# cpu_board.net
KiCad netlist of a schematic drawn in EAGLE
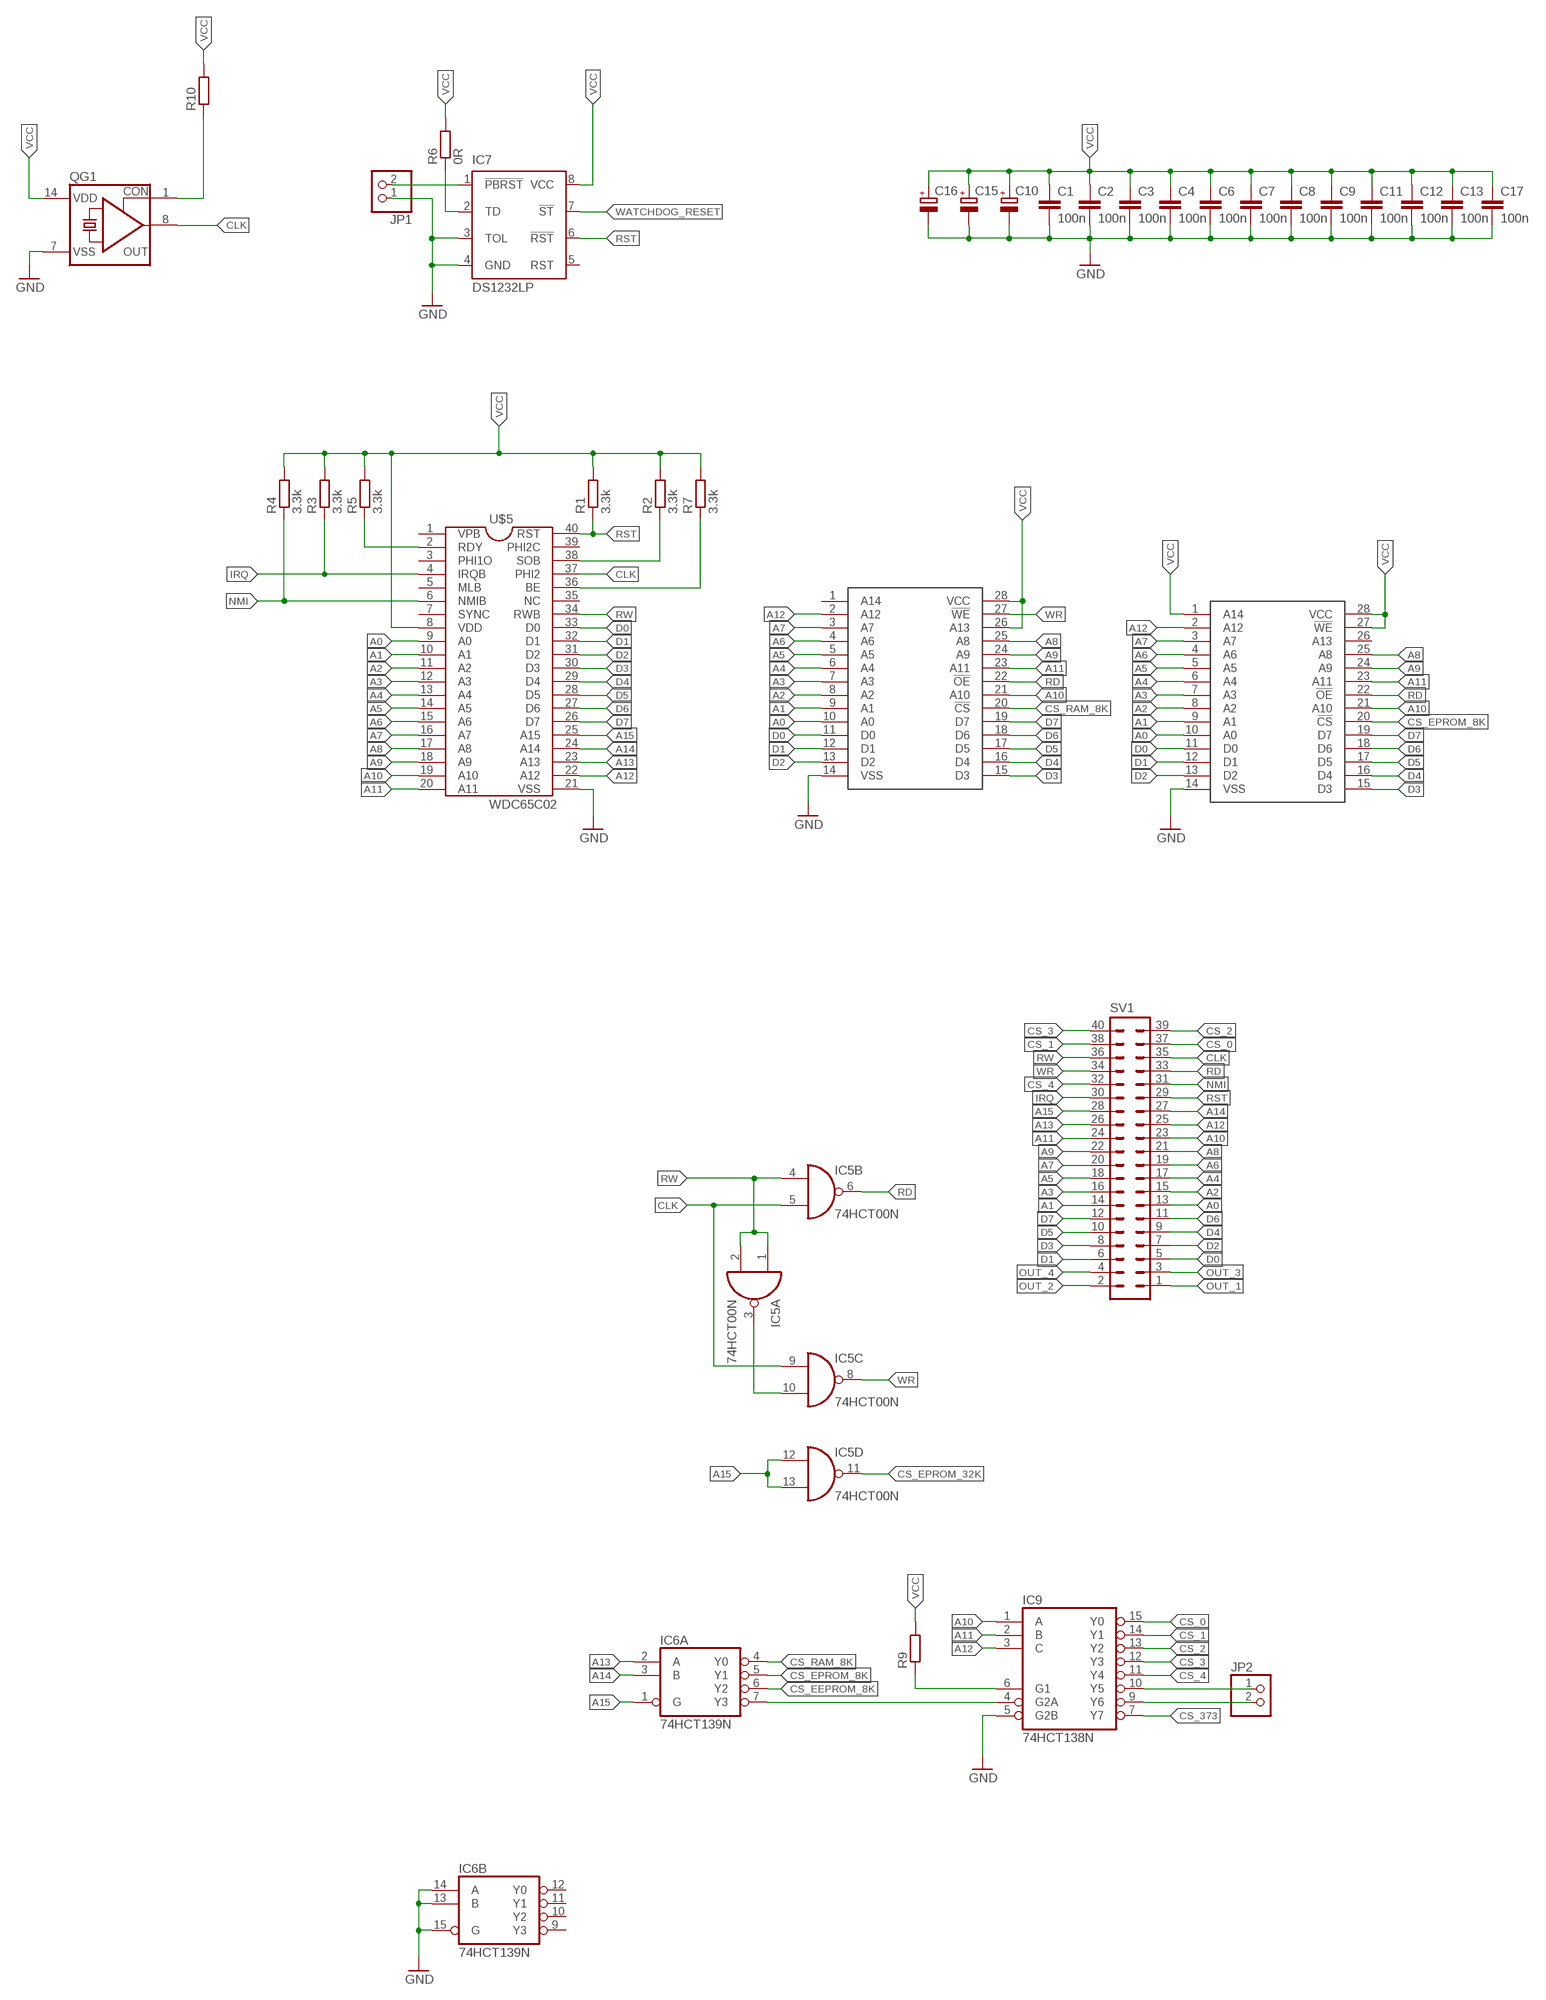
[diagram p0: schematic, sheet 1, part 1 of 2]
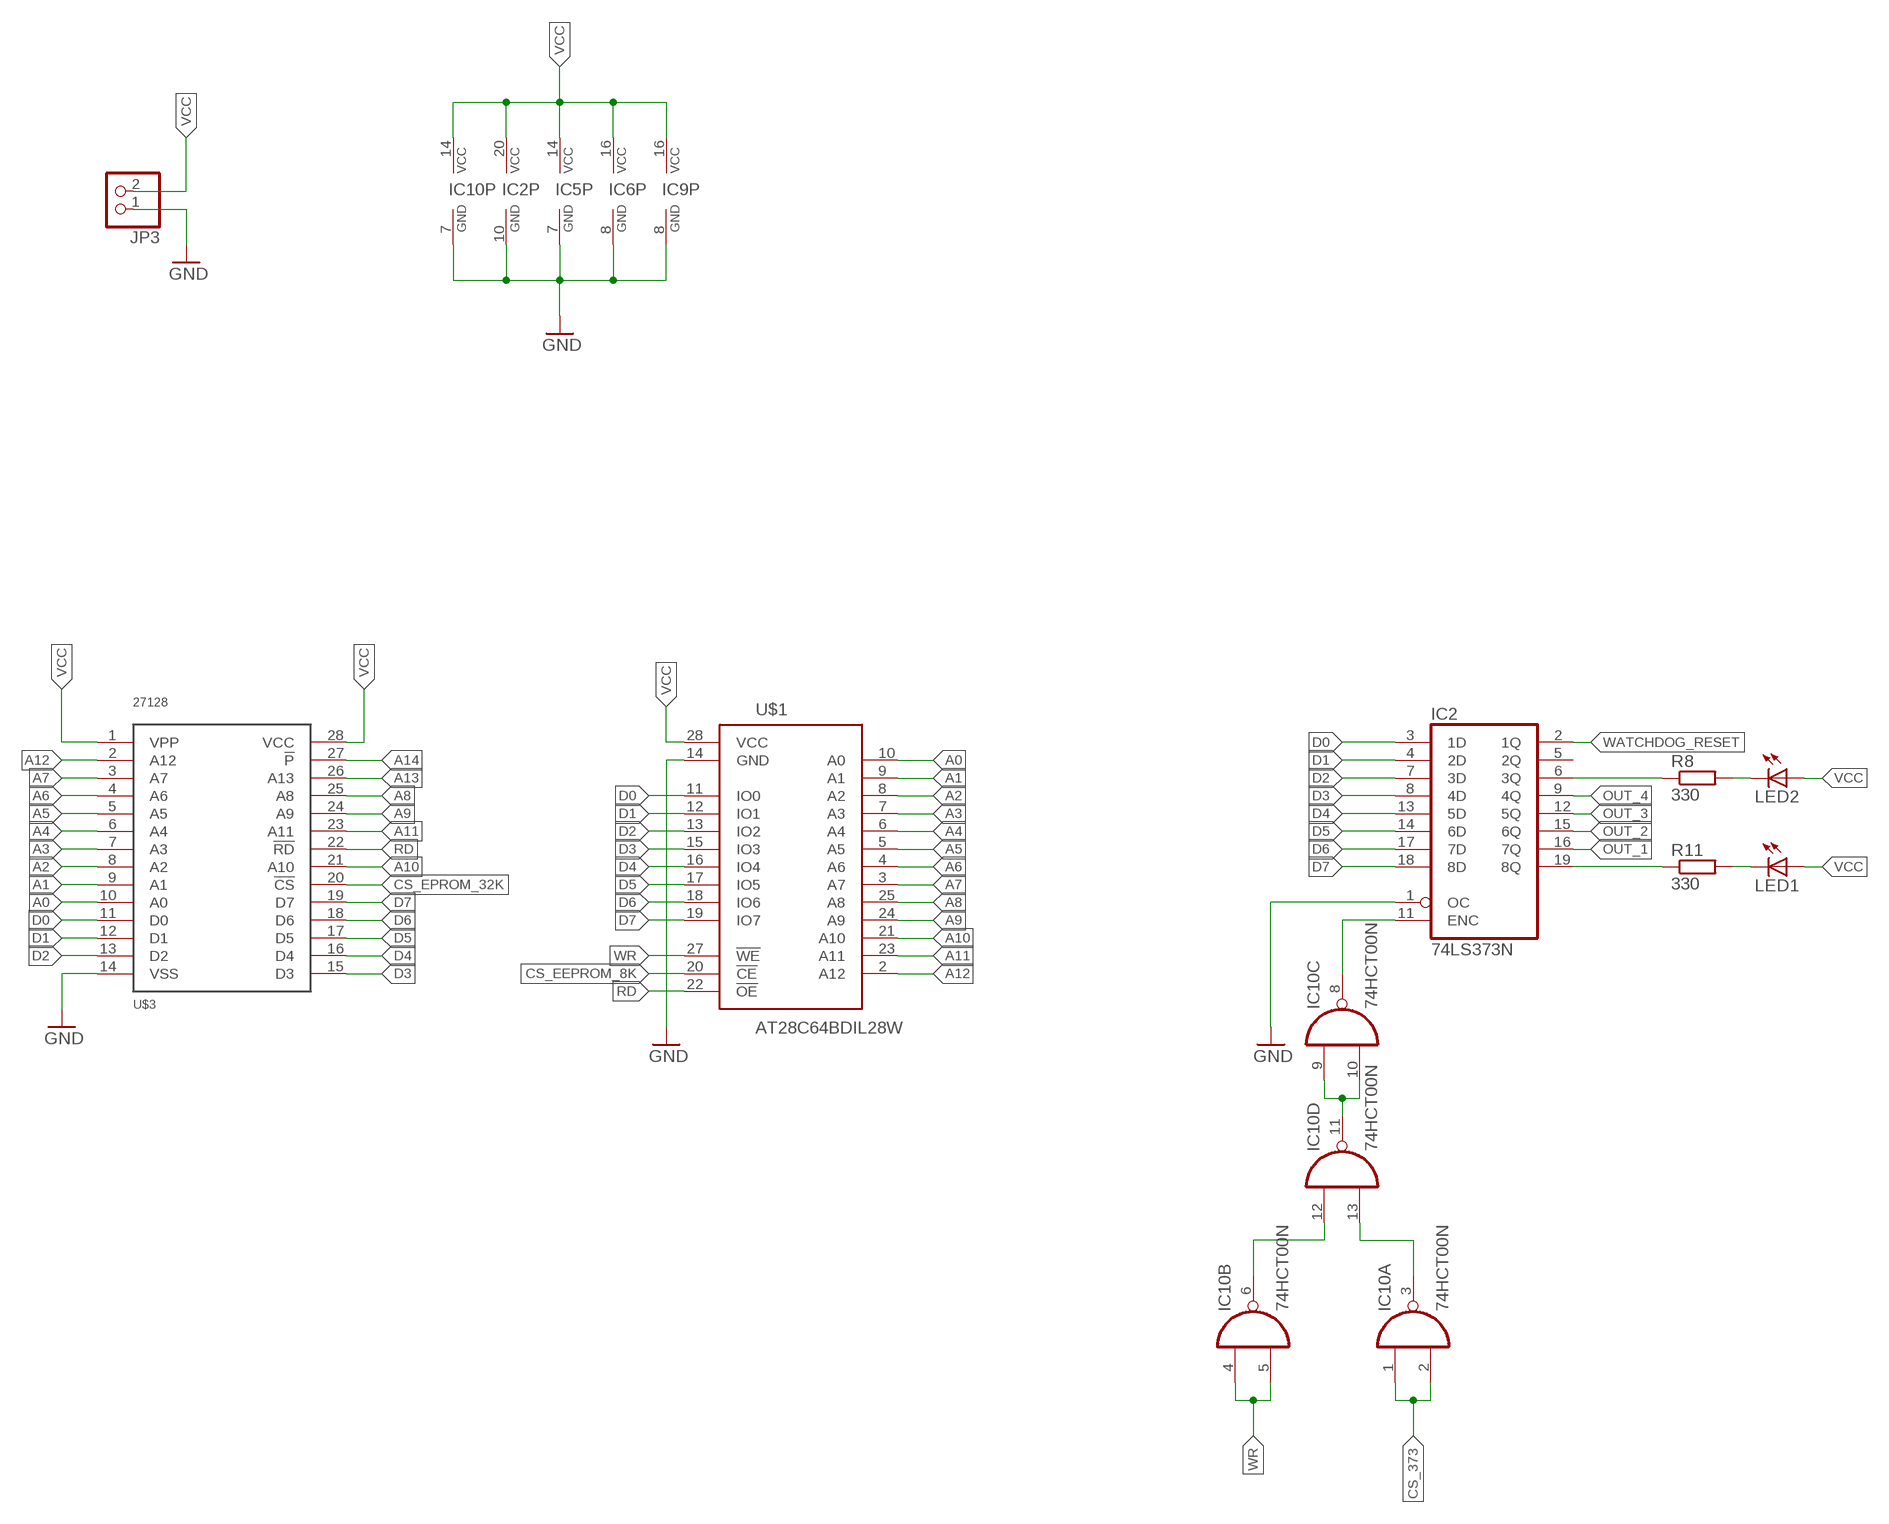
[diagram p1: schematic, sheet 1, part 2 of 2]

(export (version "E")
  (design (tool "Eeschema 10.0.6"))
  (components
    (comp (ref "C1")
      (value "100n")
      (footprint "eagle-import:C1206")
      (libsource (lib "eagle-import") (part "C-EUC1206"))
    )
    (comp (ref "C2")
      (value "100n")
      (footprint "eagle-import:C1206")
      (libsource (lib "eagle-import") (part "C-EUC1206"))
    )
    (comp (ref "C3")
      (value "100n")
      (footprint "eagle-import:C1206")
      (libsource (lib "eagle-import") (part "C-EUC1206"))
    )
    (comp (ref "C4")
      (value "100n")
      (footprint "eagle-import:C1206")
      (libsource (lib "eagle-import") (part "C-EUC1206"))
    )
    (comp (ref "C6")
      (value "100n")
      (footprint "eagle-import:C1206")
      (libsource (lib "eagle-import") (part "C-EUC1206"))
    )
    (comp (ref "C7")
      (value "100n")
      (footprint "eagle-import:C1206")
      (libsource (lib "eagle-import") (part "C-EUC1206"))
    )
    (comp (ref "C8")
      (value "100n")
      (footprint "eagle-import:C1206")
      (libsource (lib "eagle-import") (part "C-EUC1206"))
    )
    (comp (ref "C9")
      (value "100n")
      (footprint "eagle-import:C1206")
      (libsource (lib "eagle-import") (part "C-EUC1206"))
    )
    (comp (ref "C10")
      (value "CPOL-EUE5-10.5")
      (footprint "eagle-import:E5-10,5")
      (libsource (lib "eagle-import") (part "CPOL-EUE5-10.5"))
    )
    (comp (ref "C11")
      (value "100n")
      (footprint "eagle-import:C0805")
      (libsource (lib "eagle-import") (part "C-EUC0805"))
    )
    (comp (ref "C12")
      (value "100n")
      (footprint "eagle-import:C0805")
      (libsource (lib "eagle-import") (part "C-EUC0805"))
    )
    (comp (ref "C13")
      (value "100n")
      (footprint "eagle-import:C0805")
      (libsource (lib "eagle-import") (part "C-EUC0805"))
    )
    (comp (ref "C15")
      (value "CPOL-EUSMCB")
      (footprint "eagle-import:SMC_B")
      (libsource (lib "eagle-import") (part "CPOL-EUSMCB"))
    )
    (comp (ref "C16")
      (value "CPOL-EUSMCB")
      (footprint "eagle-import:SMC_B")
      (libsource (lib "eagle-import") (part "CPOL-EUSMCB"))
    )
    (comp (ref "C17")
      (value "100n")
      (footprint "eagle-import:C1206")
      (libsource (lib "eagle-import") (part "C-EUC1206"))
    )
    (comp (ref "IC2")
      (value "74LS373N")
      (footprint "eagle-import:DIL20")
      (libsource (lib "eagle-import") (part "74373NLS"))
    )
    (comp (ref "IC5")
      (value "74HCT00N")
      (footprint "eagle-import:DIL14")
      (libsource (lib "eagle-import") (part "7400NHCT"))
    )
    (comp (ref "IC6")
      (value "74HCT139N")
      (footprint "eagle-import:DIL16")
      (libsource (lib "eagle-import") (part "74139NHCT"))
    )
    (comp (ref "IC7")
      (value "DS1232LP")
      (footprint "eagle-import:DIL08")
      (fields (field (name "MPN") "DS1232LP+"))
      (libsource (lib "eagle-import") (part "DS1232LP"))
    )
    (comp (ref "IC9")
      (value "74HCT138N")
      (footprint "eagle-import:DIL16")
      (libsource (lib "eagle-import") (part "74138NHCT"))
    )
    (comp (ref "IC10")
      (value "74HCT00N")
      (footprint "eagle-import:DIL14")
      (libsource (lib "eagle-import") (part "7400NHCT"))
    )
    (comp (ref "JP1")
      (value "PINHD-1X2")
      (footprint "eagle-import:1X02")
      (libsource (lib "eagle-import") (part "PINHD-1X2"))
    )
    (comp (ref "JP2")
      (value "PINHD-1X2")
      (footprint "eagle-import:1X02")
      (libsource (lib "eagle-import") (part "PINHD-1X2"))
    )
    (comp (ref "JP3")
      (value "PINHD-1X2/90")
      (footprint "eagle-import:1X02_90")
      (libsource (lib "eagle-import") (part "PINHD-1X2/90"))
    )
    (comp (ref "LED1")
      (value "LED5MM")
      (footprint "eagle-import:LED5MM")
      (libsource (lib "eagle-import") (part "LED5MM"))
    )
    (comp (ref "LED2")
      (value "LED5MM")
      (footprint "eagle-import:LED5MM")
      (libsource (lib "eagle-import") (part "LED5MM"))
    )
    (comp (ref "QG1")
      (value "CRYSTAL_RES-SG51")
      (footprint "eagle-import:SG51")
      (libsource (lib "eagle-import") (part "CRYSTAL_RES-SG51"))
    )
    (comp (ref "R1")
      (value "3.3k")
      (footprint "eagle-import:R1206")
      (libsource (lib "eagle-import") (part "R-EU_R1206"))
    )
    (comp (ref "R2")
      (value "3.3k")
      (footprint "eagle-import:R1206")
      (libsource (lib "eagle-import") (part "R-EU_R1206"))
    )
    (comp (ref "R3")
      (value "3.3k")
      (footprint "eagle-import:R1206")
      (libsource (lib "eagle-import") (part "R-EU_R1206"))
    )
    (comp (ref "R4")
      (value "3.3k")
      (footprint "eagle-import:R1206")
      (libsource (lib "eagle-import") (part "R-EU_R1206"))
    )
    (comp (ref "R5")
      (value "3.3k")
      (footprint "eagle-import:R1206")
      (libsource (lib "eagle-import") (part "R-EU_R1206"))
    )
    (comp (ref "R6")
      (value "0R")
      (footprint "eagle-import:R1206")
      (libsource (lib "eagle-import") (part "R-EU_R1206"))
    )
    (comp (ref "R7")
      (value "3.3k")
      (footprint "eagle-import:R1206")
      (libsource (lib "eagle-import") (part "R-EU_R1206"))
    )
    (comp (ref "R8")
      (value "330")
      (footprint "eagle-import:R1206")
      (libsource (lib "eagle-import") (part "R-EU_R1206"))
    )
    (comp (ref "R9")
      (value "R-EU_0204/7")
      (footprint "eagle-import:0204_7")
      (libsource (lib "eagle-import") (part "R-EU_0204/7"))
    )
    (comp (ref "R10")
      (value "R-EU_R1206")
      (footprint "eagle-import:R1206")
      (libsource (lib "eagle-import") (part "R-EU_R1206"))
    )
    (comp (ref "R11")
      (value "330")
      (footprint "eagle-import:R1206")
      (libsource (lib "eagle-import") (part "R-EU_R1206"))
    )
    (comp (ref "SV1")
      (value "ML40L")
      (footprint "eagle-import:ML40L")
      (libsource (lib "eagle-import") (part "ML40L"))
    )
    (comp (ref "U$1")
      (value "AT28C64BDIL28W")
      (footprint "eagle-import:DIL28-6")
      (libsource (lib "eagle-import") (part "AT28C64BDIL28W"))
    )
    (comp (ref "U$2")
      (value "62256")
      (footprint "eagle-import:DIL28-6")
      (libsource (lib "eagle-import") (part "62256"))
    )
    (comp (ref "U$3")
      (value "27128")
      (footprint "eagle-import:DIL28")
      (libsource (lib "eagle-import") (part "27128"))
    )
    (comp (ref "U$4")
      (value "62256")
      (footprint "eagle-import:DIL28-6")
      (libsource (lib "eagle-import") (part "62256"))
    )
    (comp (ref "U$5")
      (value "WDC65C02")
      (footprint "eagle-import:DIL40")
      (libsource (lib "eagle-import") (part "WDC65C02"))
    )
  )
  (nets
    (net (code "1") (name "A0") (class "Default")
      (node (ref "SV1") (pin "13") (pinfunction "13_13") (pintype "passive"))
      (node (ref "U$1") (pin "10") (pinfunction "A0_10") (pintype "bidirectional"))
      (node (ref "U$2") (pin "10") (pinfunction "A0_10") (pintype "bidirectional"))
      (node (ref "U$3") (pin "10") (pinfunction "A0_10") (pintype "bidirectional"))
      (node (ref "U$4") (pin "10") (pinfunction "A0_10") (pintype "bidirectional"))
      (node (ref "U$5") (pin "9") (pinfunction "A0_9") (pintype "bidirectional"))
    )
    (net (code "2") (name "A1") (class "Default")
      (node (ref "SV1") (pin "14") (pinfunction "14_14") (pintype "passive"))
      (node (ref "U$1") (pin "9") (pinfunction "A1_9") (pintype "bidirectional"))
      (node (ref "U$2") (pin "9") (pinfunction "A1_9") (pintype "bidirectional"))
      (node (ref "U$3") (pin "9") (pinfunction "A1_9") (pintype "bidirectional"))
      (node (ref "U$4") (pin "9") (pinfunction "A1_9") (pintype "bidirectional"))
      (node (ref "U$5") (pin "10") (pinfunction "A1_10") (pintype "bidirectional"))
    )
    (net (code "3") (name "A2") (class "Default")
      (node (ref "SV1") (pin "15") (pinfunction "15_15") (pintype "passive"))
      (node (ref "U$1") (pin "8") (pinfunction "A2_8") (pintype "bidirectional"))
      (node (ref "U$2") (pin "8") (pinfunction "A2_8") (pintype "bidirectional"))
      (node (ref "U$3") (pin "8") (pinfunction "A2_8") (pintype "bidirectional"))
      (node (ref "U$4") (pin "8") (pinfunction "A2_8") (pintype "bidirectional"))
      (node (ref "U$5") (pin "11") (pinfunction "A2_11") (pintype "bidirectional"))
    )
    (net (code "4") (name "A3") (class "Default")
      (node (ref "SV1") (pin "16") (pinfunction "16_16") (pintype "passive"))
      (node (ref "U$1") (pin "7") (pinfunction "A3_7") (pintype "bidirectional"))
      (node (ref "U$2") (pin "7") (pinfunction "A3_7") (pintype "bidirectional"))
      (node (ref "U$3") (pin "7") (pinfunction "A3_7") (pintype "bidirectional"))
      (node (ref "U$4") (pin "7") (pinfunction "A3_7") (pintype "bidirectional"))
      (node (ref "U$5") (pin "12") (pinfunction "A3_12") (pintype "bidirectional"))
    )
    (net (code "5") (name "A4") (class "Default")
      (node (ref "SV1") (pin "17") (pinfunction "17_17") (pintype "passive"))
      (node (ref "U$1") (pin "6") (pinfunction "A4_6") (pintype "bidirectional"))
      (node (ref "U$2") (pin "6") (pinfunction "A4_6") (pintype "bidirectional"))
      (node (ref "U$3") (pin "6") (pinfunction "A4_6") (pintype "bidirectional"))
      (node (ref "U$4") (pin "6") (pinfunction "A4_6") (pintype "bidirectional"))
      (node (ref "U$5") (pin "13") (pinfunction "A4_13") (pintype "bidirectional"))
    )
    (net (code "6") (name "A5") (class "Default")
      (node (ref "SV1") (pin "18") (pinfunction "18_18") (pintype "passive"))
      (node (ref "U$1") (pin "5") (pinfunction "A5_5") (pintype "bidirectional"))
      (node (ref "U$2") (pin "5") (pinfunction "A5_5") (pintype "bidirectional"))
      (node (ref "U$3") (pin "5") (pinfunction "A5_5") (pintype "bidirectional"))
      (node (ref "U$4") (pin "5") (pinfunction "A5_5") (pintype "bidirectional"))
      (node (ref "U$5") (pin "14") (pinfunction "A5_14") (pintype "bidirectional"))
    )
    (net (code "7") (name "A6") (class "Default")
      (node (ref "SV1") (pin "19") (pinfunction "19_19") (pintype "passive"))
      (node (ref "U$1") (pin "4") (pinfunction "A6_4") (pintype "bidirectional"))
      (node (ref "U$2") (pin "4") (pinfunction "A6_4") (pintype "bidirectional"))
      (node (ref "U$3") (pin "4") (pinfunction "A6_4") (pintype "bidirectional"))
      (node (ref "U$4") (pin "4") (pinfunction "A6_4") (pintype "bidirectional"))
      (node (ref "U$5") (pin "15") (pinfunction "A6_15") (pintype "bidirectional"))
    )
    (net (code "8") (name "A7") (class "Default")
      (node (ref "SV1") (pin "20") (pinfunction "20_20") (pintype "passive"))
      (node (ref "U$1") (pin "3") (pinfunction "A7_3") (pintype "bidirectional"))
      (node (ref "U$2") (pin "3") (pinfunction "A7_3") (pintype "bidirectional"))
      (node (ref "U$3") (pin "3") (pinfunction "A7_3") (pintype "bidirectional"))
      (node (ref "U$4") (pin "3") (pinfunction "A7_3") (pintype "bidirectional"))
      (node (ref "U$5") (pin "16") (pinfunction "A7_16") (pintype "bidirectional"))
    )
    (net (code "9") (name "A8") (class "Default")
      (node (ref "SV1") (pin "21") (pinfunction "21_21") (pintype "passive"))
      (node (ref "U$1") (pin "25") (pinfunction "A8_25") (pintype "bidirectional"))
      (node (ref "U$2") (pin "25") (pinfunction "A8_25") (pintype "bidirectional"))
      (node (ref "U$3") (pin "25") (pinfunction "A8_25") (pintype "bidirectional"))
      (node (ref "U$4") (pin "25") (pinfunction "A8_25") (pintype "bidirectional"))
      (node (ref "U$5") (pin "17") (pinfunction "A8_17") (pintype "bidirectional"))
    )
    (net (code "10") (name "A9") (class "Default")
      (node (ref "SV1") (pin "22") (pinfunction "22_22") (pintype "passive"))
      (node (ref "U$1") (pin "24") (pinfunction "A9_24") (pintype "bidirectional"))
      (node (ref "U$2") (pin "24") (pinfunction "A9_24") (pintype "bidirectional"))
      (node (ref "U$3") (pin "24") (pinfunction "A9_24") (pintype "bidirectional"))
      (node (ref "U$4") (pin "24") (pinfunction "A9_24") (pintype "bidirectional"))
      (node (ref "U$5") (pin "18") (pinfunction "A9_18") (pintype "bidirectional"))
    )
    (net (code "11") (name "A10") (class "Default")
      (node (ref "IC9") (pin "1") (pinfunction "A_1") (pintype "input"))
      (node (ref "SV1") (pin "23") (pinfunction "23_23") (pintype "passive"))
      (node (ref "U$1") (pin "21") (pinfunction "A10_21") (pintype "bidirectional"))
      (node (ref "U$2") (pin "21") (pinfunction "A10_21") (pintype "bidirectional"))
      (node (ref "U$3") (pin "21") (pinfunction "A10_21") (pintype "bidirectional"))
      (node (ref "U$4") (pin "21") (pinfunction "A10_21") (pintype "bidirectional"))
      (node (ref "U$5") (pin "19") (pinfunction "A10_19") (pintype "bidirectional"))
    )
    (net (code "12") (name "A11") (class "Default")
      (node (ref "IC9") (pin "2") (pinfunction "B_2") (pintype "input"))
      (node (ref "SV1") (pin "24") (pinfunction "24_24") (pintype "passive"))
      (node (ref "U$1") (pin "23") (pinfunction "A11_23") (pintype "bidirectional"))
      (node (ref "U$2") (pin "23") (pinfunction "A11_23") (pintype "bidirectional"))
      (node (ref "U$3") (pin "23") (pinfunction "A11_23") (pintype "bidirectional"))
      (node (ref "U$4") (pin "23") (pinfunction "A11_23") (pintype "bidirectional"))
      (node (ref "U$5") (pin "20") (pinfunction "A11_20") (pintype "bidirectional"))
    )
    (net (code "13") (name "A12") (class "Default")
      (node (ref "IC9") (pin "3") (pinfunction "C_3") (pintype "input"))
      (node (ref "SV1") (pin "25") (pinfunction "25_25") (pintype "passive"))
      (node (ref "U$1") (pin "2") (pinfunction "A12_2") (pintype "bidirectional"))
      (node (ref "U$2") (pin "2") (pinfunction "A12_2") (pintype "bidirectional"))
      (node (ref "U$3") (pin "2") (pinfunction "A12_2") (pintype "bidirectional"))
      (node (ref "U$4") (pin "2") (pinfunction "A12_2") (pintype "bidirectional"))
      (node (ref "U$5") (pin "22") (pinfunction "A12_22") (pintype "bidirectional"))
    )
    (net (code "14") (name "A13") (class "Default")
      (node (ref "IC6") (pin "2") (pinfunction "A_2") (pintype "input"))
      (node (ref "SV1") (pin "26") (pinfunction "26_26") (pintype "passive"))
      (node (ref "U$3") (pin "26") (pinfunction "A13_26") (pintype "bidirectional"))
      (node (ref "U$5") (pin "23") (pinfunction "A13_23") (pintype "bidirectional"))
    )
    (net (code "15") (name "A14") (class "Default")
      (node (ref "IC6") (pin "3") (pinfunction "B_3") (pintype "input"))
      (node (ref "SV1") (pin "27") (pinfunction "27_27") (pintype "passive"))
      (node (ref "U$3") (pin "27") (pinfunction "~{P}_27") (pintype "bidirectional"))
      (node (ref "U$5") (pin "24") (pinfunction "A14_24") (pintype "bidirectional"))
    )
    (net (code "16") (name "A15") (class "Default")
      (node (ref "IC5") (pin "12") (pinfunction "I0_12") (pintype "input"))
      (node (ref "IC5") (pin "13") (pinfunction "I1_13") (pintype "input"))
      (node (ref "IC6") (pin "1") (pinfunction "G_1") (pintype "input"))
      (node (ref "SV1") (pin "28") (pinfunction "28_28") (pintype "passive"))
      (node (ref "U$5") (pin "25") (pinfunction "A15_25") (pintype "bidirectional"))
    )
    (net (code "17") (name "CLK") (class "Default")
      (node (ref "IC5") (pin "5") (pinfunction "I1_5") (pintype "input"))
      (node (ref "IC5") (pin "9") (pinfunction "I0_9") (pintype "input"))
      (node (ref "QG1") (pin "8") (pinfunction "OUT_8") (pintype "output"))
      (node (ref "SV1") (pin "35") (pinfunction "35_35") (pintype "passive"))
      (node (ref "U$5") (pin "37") (pinfunction "PHI2_37") (pintype "bidirectional"))
    )
    (net (code "18") (name "CS_0") (class "Default")
      (node (ref "IC9") (pin "15") (pinfunction "Y0_15") (pintype "output"))
      (node (ref "SV1") (pin "37") (pinfunction "37_37") (pintype "passive"))
    )
    (net (code "19") (name "CS_1") (class "Default")
      (node (ref "IC9") (pin "14") (pinfunction "Y1_14") (pintype "output"))
      (node (ref "SV1") (pin "38") (pinfunction "38_38") (pintype "passive"))
    )
    (net (code "20") (name "CS_2") (class "Default")
      (node (ref "IC9") (pin "13") (pinfunction "Y2_13") (pintype "output"))
      (node (ref "SV1") (pin "39") (pinfunction "39_39") (pintype "passive"))
    )
    (net (code "21") (name "CS_3") (class "Default")
      (node (ref "IC9") (pin "12") (pinfunction "Y3_12") (pintype "output"))
      (node (ref "SV1") (pin "40") (pinfunction "40_40") (pintype "passive"))
    )
    (net (code "22") (name "CS_4") (class "Default")
      (node (ref "IC9") (pin "11") (pinfunction "Y4_11") (pintype "output"))
      (node (ref "SV1") (pin "32") (pinfunction "32_32") (pintype "passive"))
    )
    (net (code "23") (name "CS_373") (class "Default")
      (node (ref "IC10") (pin "1") (pinfunction "I0_1") (pintype "input"))
      (node (ref "IC10") (pin "2") (pinfunction "I1_2") (pintype "input"))
      (node (ref "IC9") (pin "7") (pinfunction "Y7_7") (pintype "output"))
    )
    (net (code "24") (name "CS_EEPROM_8K") (class "Default")
      (node (ref "IC6") (pin "6") (pinfunction "Y2_6") (pintype "output"))
      (node (ref "U$1") (pin "20") (pinfunction "~{CE}_20") (pintype "bidirectional"))
    )
    (net (code "25") (name "CS_EPROM_8K") (class "Default")
      (node (ref "IC6") (pin "5") (pinfunction "Y1_5") (pintype "output"))
      (node (ref "U$2") (pin "20") (pinfunction "~{CS}_20") (pintype "bidirectional"))
    )
    (net (code "26") (name "CS_EPROM_32K") (class "Default")
      (node (ref "IC5") (pin "11") (pinfunction "O_11") (pintype "output"))
      (node (ref "U$3") (pin "20") (pinfunction "~{CS}_20") (pintype "bidirectional"))
    )
    (net (code "27") (name "CS_RAM_8K") (class "Default")
      (node (ref "IC6") (pin "4") (pinfunction "Y0_4") (pintype "output"))
      (node (ref "U$4") (pin "20") (pinfunction "~{CS}_20") (pintype "bidirectional"))
    )
    (net (code "28") (name "D0") (class "Default")
      (node (ref "IC2") (pin "3") (pinfunction "1D_3") (pintype "input"))
      (node (ref "SV1") (pin "5") (pinfunction "5_5") (pintype "passive"))
      (node (ref "U$1") (pin "11") (pinfunction "IO0_11") (pintype "bidirectional"))
      (node (ref "U$2") (pin "11") (pinfunction "D0_11") (pintype "bidirectional"))
      (node (ref "U$3") (pin "11") (pinfunction "D0_11") (pintype "bidirectional"))
      (node (ref "U$4") (pin "11") (pinfunction "D0_11") (pintype "bidirectional"))
      (node (ref "U$5") (pin "33") (pinfunction "D0_33") (pintype "bidirectional"))
    )
    (net (code "29") (name "D1") (class "Default")
      (node (ref "IC2") (pin "4") (pinfunction "2D_4") (pintype "input"))
      (node (ref "SV1") (pin "6") (pinfunction "6_6") (pintype "passive"))
      (node (ref "U$1") (pin "12") (pinfunction "IO1_12") (pintype "bidirectional"))
      (node (ref "U$2") (pin "12") (pinfunction "D1_12") (pintype "bidirectional"))
      (node (ref "U$3") (pin "12") (pinfunction "D1_12") (pintype "bidirectional"))
      (node (ref "U$4") (pin "12") (pinfunction "D1_12") (pintype "bidirectional"))
      (node (ref "U$5") (pin "32") (pinfunction "D1_32") (pintype "bidirectional"))
    )
    (net (code "30") (name "D2") (class "Default")
      (node (ref "IC2") (pin "7") (pinfunction "3D_7") (pintype "input"))
      (node (ref "SV1") (pin "7") (pinfunction "7_7") (pintype "passive"))
      (node (ref "U$1") (pin "13") (pinfunction "IO2_13") (pintype "bidirectional"))
      (node (ref "U$2") (pin "13") (pinfunction "D2_13") (pintype "bidirectional"))
      (node (ref "U$3") (pin "13") (pinfunction "D2_13") (pintype "bidirectional"))
      (node (ref "U$4") (pin "13") (pinfunction "D2_13") (pintype "bidirectional"))
      (node (ref "U$5") (pin "31") (pinfunction "D2_31") (pintype "bidirectional"))
    )
    (net (code "31") (name "D3") (class "Default")
      (node (ref "IC2") (pin "8") (pinfunction "4D_8") (pintype "input"))
      (node (ref "SV1") (pin "8") (pinfunction "8_8") (pintype "passive"))
      (node (ref "U$1") (pin "15") (pinfunction "IO3_15") (pintype "bidirectional"))
      (node (ref "U$2") (pin "15") (pinfunction "D3_15") (pintype "bidirectional"))
      (node (ref "U$3") (pin "15") (pinfunction "D3_15") (pintype "bidirectional"))
      (node (ref "U$4") (pin "15") (pinfunction "D3_15") (pintype "bidirectional"))
      (node (ref "U$5") (pin "30") (pinfunction "D3_30") (pintype "bidirectional"))
    )
    (net (code "32") (name "D4") (class "Default")
      (node (ref "IC2") (pin "13") (pinfunction "5D_13") (pintype "input"))
      (node (ref "SV1") (pin "9") (pinfunction "9_9") (pintype "passive"))
      (node (ref "U$1") (pin "16") (pinfunction "IO4_16") (pintype "bidirectional"))
      (node (ref "U$2") (pin "16") (pinfunction "D4_16") (pintype "bidirectional"))
      (node (ref "U$3") (pin "16") (pinfunction "D4_16") (pintype "bidirectional"))
      (node (ref "U$4") (pin "16") (pinfunction "D4_16") (pintype "bidirectional"))
      (node (ref "U$5") (pin "29") (pinfunction "D4_29") (pintype "bidirectional"))
    )
    (net (code "33") (name "D5") (class "Default")
      (node (ref "IC2") (pin "14") (pinfunction "6D_14") (pintype "input"))
      (node (ref "SV1") (pin "10") (pinfunction "10_10") (pintype "passive"))
      (node (ref "U$1") (pin "17") (pinfunction "IO5_17") (pintype "bidirectional"))
      (node (ref "U$2") (pin "17") (pinfunction "D5_17") (pintype "bidirectional"))
      (node (ref "U$3") (pin "17") (pinfunction "D5_17") (pintype "bidirectional"))
      (node (ref "U$4") (pin "17") (pinfunction "D5_17") (pintype "bidirectional"))
      (node (ref "U$5") (pin "28") (pinfunction "D5_28") (pintype "bidirectional"))
    )
    (net (code "34") (name "D6") (class "Default")
      (node (ref "IC2") (pin "17") (pinfunction "7D_17") (pintype "input"))
      (node (ref "SV1") (pin "11") (pinfunction "11_11") (pintype "passive"))
      (node (ref "U$1") (pin "18") (pinfunction "IO6_18") (pintype "bidirectional"))
      (node (ref "U$2") (pin "18") (pinfunction "D6_18") (pintype "bidirectional"))
      (node (ref "U$3") (pin "18") (pinfunction "D6_18") (pintype "bidirectional"))
      (node (ref "U$4") (pin "18") (pinfunction "D6_18") (pintype "bidirectional"))
      (node (ref "U$5") (pin "27") (pinfunction "D6_27") (pintype "bidirectional"))
    )
    (net (code "35") (name "D7") (class "Default")
      (node (ref "IC2") (pin "18") (pinfunction "8D_18") (pintype "input"))
      (node (ref "SV1") (pin "12") (pinfunction "12_12") (pintype "passive"))
      (node (ref "U$1") (pin "19") (pinfunction "IO7_19") (pintype "bidirectional"))
      (node (ref "U$2") (pin "19") (pinfunction "D7_19") (pintype "bidirectional"))
      (node (ref "U$3") (pin "19") (pinfunction "D7_19") (pintype "bidirectional"))
      (node (ref "U$4") (pin "19") (pinfunction "D7_19") (pintype "bidirectional"))
      (node (ref "U$5") (pin "26") (pinfunction "D7_26") (pintype "bidirectional"))
    )
    (net (code "36") (name "GND") (class "Default")
      (node (ref "C1") (pin "2") (pinfunction "2_2") (pintype "passive"))
      (node (ref "C10") (pin "-") (pinfunction "-_-") (pintype "passive"))
      (node (ref "C11") (pin "2") (pinfunction "2_2") (pintype "passive"))
      (node (ref "C12") (pin "2") (pinfunction "2_2") (pintype "passive"))
      (node (ref "C13") (pin "2") (pinfunction "2_2") (pintype "passive"))
      (node (ref "C15") (pin "-") (pinfunction "-_-") (pintype "passive"))
      (node (ref "C16") (pin "-") (pinfunction "-_-") (pintype "passive"))
      (node (ref "C17") (pin "2") (pinfunction "2_2") (pintype "passive"))
      (node (ref "C2") (pin "2") (pinfunction "2_2") (pintype "passive"))
      (node (ref "C3") (pin "2") (pinfunction "2_2") (pintype "passive"))
      (node (ref "C4") (pin "2") (pinfunction "2_2") (pintype "passive"))
      (node (ref "C6") (pin "2") (pinfunction "2_2") (pintype "passive"))
      (node (ref "C7") (pin "2") (pinfunction "2_2") (pintype "passive"))
      (node (ref "C8") (pin "2") (pinfunction "2_2") (pintype "passive"))
      (node (ref "C9") (pin "2") (pinfunction "2_2") (pintype "passive"))
      (node (ref "IC10") (pin "7") (pinfunction "GND_7") (pintype "power_in"))
      (node (ref "IC2") (pin "1") (pinfunction "OC_1") (pintype "input"))
      (node (ref "IC2") (pin "10") (pinfunction "GND_10") (pintype "power_in"))
      (node (ref "IC5") (pin "7") (pinfunction "GND_7") (pintype "power_in"))
      (node (ref "IC6") (pin "13") (pinfunction "B_13") (pintype "input"))
      (node (ref "IC6") (pin "14") (pinfunction "A_14") (pintype "input"))
      (node (ref "IC6") (pin "15") (pinfunction "G_15") (pintype "input"))
      (node (ref "IC6") (pin "8") (pinfunction "GND_8") (pintype "power_in"))
      (node (ref "IC7") (pin "3") (pinfunction "TOL_3") (pintype "input"))
      (node (ref "IC7") (pin "4") (pinfunction "GND_4") (pintype "power_in"))
      (node (ref "IC9") (pin "5") (pinfunction "G2B_5") (pintype "input"))
      (node (ref "IC9") (pin "8") (pinfunction "GND_8") (pintype "power_in"))
      (node (ref "JP1") (pin "1") (pinfunction "1_1") (pintype "passive"))
      (node (ref "JP3") (pin "1") (pinfunction "1_1") (pintype "passive"))
      (node (ref "QG1") (pin "7") (pinfunction "VSS_7") (pintype "power_in"))
      (node (ref "U$1") (pin "14") (pinfunction "GND_14") (pintype "bidirectional"))
      (node (ref "U$2") (pin "14") (pinfunction "VSS_14") (pintype "bidirectional"))
      (node (ref "U$3") (pin "14") (pinfunction "VSS_14") (pintype "bidirectional"))
      (node (ref "U$4") (pin "14") (pinfunction "VSS_14") (pintype "bidirectional"))
      (node (ref "U$5") (pin "21") (pinfunction "VSS_21") (pintype "bidirectional"))
    )
    (net (code "37") (name "IRQ") (class "Default")
      (node (ref "R3") (pin "1") (pinfunction "1_1") (pintype "passive"))
      (node (ref "SV1") (pin "30") (pinfunction "30_30") (pintype "passive"))
      (node (ref "U$5") (pin "4") (pinfunction "IRQB_4") (pintype "bidirectional"))
    )
    (net (code "38") (name "NMI") (class "Default")
      (node (ref "R4") (pin "1") (pinfunction "1_1") (pintype "passive"))
      (node (ref "SV1") (pin "31") (pinfunction "31_31") (pintype "passive"))
      (node (ref "U$5") (pin "6") (pinfunction "NMIB_6") (pintype "bidirectional"))
    )
    (net (code "39") (name "Net-(IC2A-3Q)") (class "Default")
      (node (ref "IC2") (pin "6") (pinfunction "3Q_6") (pintype "tri_state"))
      (node (ref "R8") (pin "1") (pinfunction "1_1") (pintype "passive"))
    )
    (net (code "40") (name "Net-(IC2A-8Q)") (class "Default")
      (node (ref "IC2") (pin "19") (pinfunction "8Q_19") (pintype "tri_state"))
      (node (ref "R11") (pin "1") (pinfunction "1_1") (pintype "passive"))
    )
    (net (code "41") (name "Net-(IC5A-O)") (class "Default")
      (node (ref "IC5") (pin "10") (pinfunction "I1_10") (pintype "input"))
      (node (ref "IC5") (pin "3") (pinfunction "O_3") (pintype "output"))
    )
    (net (code "42") (name "Net-(IC6A-Y3)") (class "Default")
      (node (ref "IC6") (pin "7") (pinfunction "Y3_7") (pintype "output"))
      (node (ref "IC9") (pin "4") (pinfunction "G2A_4") (pintype "input"))
    )
    (net (code "43") (name "Net-(IC7-TD)") (class "Default")
      (node (ref "IC7") (pin "2") (pinfunction "TD_2") (pintype "input"))
      (node (ref "R6") (pin "1") (pinfunction "1_1") (pintype "passive"))
    )
    (net (code "44") (name "Net-(IC7-~{PBRST})") (class "Default")
      (node (ref "IC7") (pin "1") (pinfunction "~{PBRST}_1") (pintype "input"))
      (node (ref "JP1") (pin "2") (pinfunction "2_2") (pintype "passive"))
    )
    (net (code "45") (name "Net-(IC9A-G1)") (class "Default")
      (node (ref "IC9") (pin "6") (pinfunction "G1_6") (pintype "input"))
      (node (ref "R9") (pin "1") (pinfunction "1_1") (pintype "passive"))
    )
    (net (code "46") (name "Net-(IC9A-Y5)") (class "Default")
      (node (ref "IC9") (pin "10") (pinfunction "Y5_10") (pintype "output"))
      (node (ref "JP2") (pin "1") (pinfunction "1_1") (pintype "passive"))
    )
    (net (code "47") (name "Net-(IC9A-Y6)") (class "Default")
      (node (ref "IC9") (pin "9") (pinfunction "Y6_9") (pintype "output"))
      (node (ref "JP2") (pin "2") (pinfunction "2_2") (pintype "passive"))
    )
    (net (code "48") (name "Net-(IC10A-O)") (class "Default")
      (node (ref "IC10") (pin "13") (pinfunction "I1_13") (pintype "input"))
      (node (ref "IC10") (pin "3") (pinfunction "O_3") (pintype "output"))
    )
    (net (code "49") (name "Net-(IC10B-O)") (class "Default")
      (node (ref "IC10") (pin "12") (pinfunction "I0_12") (pintype "input"))
      (node (ref "IC10") (pin "6") (pinfunction "O_6") (pintype "output"))
    )
    (net (code "50") (name "Net-(IC10C-I0)") (class "Default")
      (node (ref "IC10") (pin "10") (pinfunction "I1_10") (pintype "input"))
      (node (ref "IC10") (pin "11") (pinfunction "O_11") (pintype "output"))
      (node (ref "IC10") (pin "9") (pinfunction "I0_9") (pintype "input"))
    )
    (net (code "51") (name "Net-(IC10C-O)") (class "Default")
      (node (ref "IC10") (pin "8") (pinfunction "O_8") (pintype "output"))
      (node (ref "IC2") (pin "11") (pinfunction "ENC_11") (pintype "input"))
    )
    (net (code "52") (name "Net-(LED1-C)") (class "Default")
      (node (ref "LED1") (pin "K") (pinfunction "C_K") (pintype "passive"))
      (node (ref "R11") (pin "2") (pinfunction "2_2") (pintype "passive"))
    )
    (net (code "53") (name "Net-(LED2-C)") (class "Default")
      (node (ref "LED2") (pin "K") (pinfunction "C_K") (pintype "passive"))
      (node (ref "R8") (pin "2") (pinfunction "2_2") (pintype "passive"))
    )
    (net (code "54") (name "Net-(QG1-CON)") (class "Default")
      (node (ref "QG1") (pin "1") (pinfunction "CON_1") (pintype "input"))
      (node (ref "R10") (pin "1") (pinfunction "1_1") (pintype "passive"))
    )
    (net (code "55") (name "Net-(U$5-BE)") (class "Default")
      (node (ref "R7") (pin "1") (pinfunction "1_1") (pintype "passive"))
      (node (ref "U$5") (pin "36") (pinfunction "BE_36") (pintype "bidirectional"))
    )
    (net (code "56") (name "Net-(U$5-RDY)") (class "Default")
      (node (ref "R5") (pin "1") (pinfunction "1_1") (pintype "passive"))
      (node (ref "U$5") (pin "2") (pinfunction "RDY_2") (pintype "bidirectional"))
    )
    (net (code "57") (name "Net-(U$5-SOB)") (class "Default")
      (node (ref "R2") (pin "1") (pinfunction "1_1") (pintype "passive"))
      (node (ref "U$5") (pin "38") (pinfunction "SOB_38") (pintype "bidirectional"))
    )
    (net (code "58") (name "OUT_1") (class "Default")
      (node (ref "IC2") (pin "16") (pinfunction "7Q_16") (pintype "tri_state"))
      (node (ref "SV1") (pin "1") (pinfunction "1_1") (pintype "passive"))
    )
    (net (code "59") (name "OUT_2") (class "Default")
      (node (ref "IC2") (pin "15") (pinfunction "6Q_15") (pintype "tri_state"))
      (node (ref "SV1") (pin "2") (pinfunction "2_2") (pintype "passive"))
    )
    (net (code "60") (name "OUT_3") (class "Default")
      (node (ref "IC2") (pin "12") (pinfunction "5Q_12") (pintype "tri_state"))
      (node (ref "SV1") (pin "3") (pinfunction "3_3") (pintype "passive"))
    )
    (net (code "61") (name "OUT_4") (class "Default")
      (node (ref "IC2") (pin "9") (pinfunction "4Q_9") (pintype "tri_state"))
      (node (ref "SV1") (pin "4") (pinfunction "4_4") (pintype "passive"))
    )
    (net (code "62") (name "RD") (class "Default")
      (node (ref "IC5") (pin "6") (pinfunction "O_6") (pintype "output"))
      (node (ref "SV1") (pin "33") (pinfunction "33_33") (pintype "passive"))
      (node (ref "U$1") (pin "22") (pinfunction "~{OE}_22") (pintype "bidirectional"))
      (node (ref "U$2") (pin "22") (pinfunction "~{OE}_22") (pintype "bidirectional"))
      (node (ref "U$3") (pin "22") (pinfunction "~{RD}_22") (pintype "bidirectional"))
      (node (ref "U$4") (pin "22") (pinfunction "~{OE}_22") (pintype "bidirectional"))
    )
    (net (code "63") (name "RST") (class "Default")
      (node (ref "IC7") (pin "6") (pinfunction "~{RST}_6") (pintype "output"))
      (node (ref "R1") (pin "1") (pinfunction "1_1") (pintype "passive"))
      (node (ref "SV1") (pin "29") (pinfunction "29_29") (pintype "passive"))
      (node (ref "U$5") (pin "40") (pinfunction "RST_40") (pintype "bidirectional"))
    )
    (net (code "64") (name "RW") (class "Default")
      (node (ref "IC5") (pin "1") (pinfunction "I0_1") (pintype "input"))
      (node (ref "IC5") (pin "2") (pinfunction "I1_2") (pintype "input"))
      (node (ref "IC5") (pin "4") (pinfunction "I0_4") (pintype "input"))
      (node (ref "SV1") (pin "36") (pinfunction "36_36") (pintype "passive"))
      (node (ref "U$5") (pin "34") (pinfunction "RWB_34") (pintype "bidirectional"))
    )
    (net (code "65") (name "VCC") (class "Default")
      (node (ref "C1") (pin "1") (pinfunction "1_1") (pintype "passive"))
      (node (ref "C10") (pin "+") (pinfunction "+_+") (pintype "passive"))
      (node (ref "C11") (pin "1") (pinfunction "1_1") (pintype "passive"))
      (node (ref "C12") (pin "1") (pinfunction "1_1") (pintype "passive"))
      (node (ref "C13") (pin "1") (pinfunction "1_1") (pintype "passive"))
      (node (ref "C15") (pin "+") (pinfunction "+_+") (pintype "passive"))
      (node (ref "C16") (pin "+") (pinfunction "+_+") (pintype "passive"))
      (node (ref "C17") (pin "1") (pinfunction "1_1") (pintype "passive"))
      (node (ref "C2") (pin "1") (pinfunction "1_1") (pintype "passive"))
      (node (ref "C3") (pin "1") (pinfunction "1_1") (pintype "passive"))
      (node (ref "C4") (pin "1") (pinfunction "1_1") (pintype "passive"))
      (node (ref "C6") (pin "1") (pinfunction "1_1") (pintype "passive"))
      (node (ref "C7") (pin "1") (pinfunction "1_1") (pintype "passive"))
      (node (ref "C8") (pin "1") (pinfunction "1_1") (pintype "passive"))
      (node (ref "C9") (pin "1") (pinfunction "1_1") (pintype "passive"))
      (node (ref "IC10") (pin "14") (pinfunction "VCC_14") (pintype "power_in"))
      (node (ref "IC2") (pin "20") (pinfunction "VCC_20") (pintype "power_in"))
      (node (ref "IC5") (pin "14") (pinfunction "VCC_14") (pintype "power_in"))
      (node (ref "IC6") (pin "16") (pinfunction "VCC_16") (pintype "power_in"))
      (node (ref "IC7") (pin "8") (pinfunction "VCC_8") (pintype "power_in"))
      (node (ref "IC9") (pin "16") (pinfunction "VCC_16") (pintype "power_in"))
      (node (ref "JP3") (pin "2") (pinfunction "2_2") (pintype "passive"))
      (node (ref "LED1") (pin "A") (pinfunction "A_A") (pintype "passive"))
      (node (ref "LED2") (pin "A") (pinfunction "A_A") (pintype "passive"))
      (node (ref "QG1") (pin "14") (pinfunction "VDD_14") (pintype "power_in"))
      (node (ref "R1") (pin "2") (pinfunction "2_2") (pintype "passive"))
      (node (ref "R10") (pin "2") (pinfunction "2_2") (pintype "passive"))
      (node (ref "R2") (pin "2") (pinfunction "2_2") (pintype "passive"))
      (node (ref "R3") (pin "2") (pinfunction "2_2") (pintype "passive"))
      (node (ref "R4") (pin "2") (pinfunction "2_2") (pintype "passive"))
      (node (ref "R5") (pin "2") (pinfunction "2_2") (pintype "passive"))
      (node (ref "R6") (pin "2") (pinfunction "2_2") (pintype "passive"))
      (node (ref "R7") (pin "2") (pinfunction "2_2") (pintype "passive"))
      (node (ref "R9") (pin "2") (pinfunction "2_2") (pintype "passive"))
      (node (ref "U$1") (pin "28") (pinfunction "VCC_28") (pintype "bidirectional"))
      (node (ref "U$2") (pin "1") (pinfunction "A14_1") (pintype "bidirectional"))
      (node (ref "U$2") (pin "27") (pinfunction "~{WE}_27") (pintype "bidirectional"))
      (node (ref "U$2") (pin "28") (pinfunction "VCC_28") (pintype "bidirectional"))
      (node (ref "U$3") (pin "1") (pinfunction "VPP_1") (pintype "bidirectional"))
      (node (ref "U$3") (pin "28") (pinfunction "VCC_28") (pintype "bidirectional"))
      (node (ref "U$4") (pin "26") (pinfunction "A13_26") (pintype "bidirectional"))
      (node (ref "U$4") (pin "28") (pinfunction "VCC_28") (pintype "bidirectional"))
      (node (ref "U$5") (pin "8") (pinfunction "VDD_8") (pintype "bidirectional"))
    )
    (net (code "66") (name "WATCHDOG_RESET") (class "Default")
      (node (ref "IC2") (pin "2") (pinfunction "1Q_2") (pintype "tri_state"))
      (node (ref "IC7") (pin "7") (pinfunction "~{ST}_7") (pintype "input"))
    )
    (net (code "67") (name "WR") (class "Default")
      (node (ref "IC10") (pin "4") (pinfunction "I0_4") (pintype "input"))
      (node (ref "IC10") (pin "5") (pinfunction "I1_5") (pintype "input"))
      (node (ref "IC5") (pin "8") (pinfunction "O_8") (pintype "output"))
      (node (ref "SV1") (pin "34") (pinfunction "34_34") (pintype "passive"))
      (node (ref "U$1") (pin "27") (pinfunction "~{WE}_27") (pintype "bidirectional"))
      (node (ref "U$4") (pin "27") (pinfunction "~{WE}_27") (pintype "bidirectional"))
    )
    (net (code "68") (name "unconnected-(IC2A-2Q-Pad5)") (class "Default")
      (node (ref "IC2") (pin "5") (pinfunction "2Q_5") (pintype "tri_state"))
    )
    (net (code "69") (name "unconnected-(IC6B-Y0-Pad12)") (class "Default")
      (node (ref "IC6") (pin "12") (pinfunction "Y0_12") (pintype "output"))
    )
    (net (code "70") (name "unconnected-(IC6B-Y1-Pad11)") (class "Default")
      (node (ref "IC6") (pin "11") (pinfunction "Y1_11") (pintype "output"))
    )
    (net (code "71") (name "unconnected-(IC6B-Y2-Pad10)") (class "Default")
      (node (ref "IC6") (pin "10") (pinfunction "Y2_10") (pintype "output"))
    )
    (net (code "72") (name "unconnected-(IC6B-Y3-Pad9)") (class "Default")
      (node (ref "IC6") (pin "9") (pinfunction "Y3_9") (pintype "output"))
    )
    (net (code "73") (name "unconnected-(IC7-RST-Pad5)") (class "Default")
      (node (ref "IC7") (pin "5") (pinfunction "RST_5") (pintype "output"))
    )
    (net (code "74") (name "unconnected-(U$2-A13-Pad26)") (class "Default")
      (node (ref "U$2") (pin "26") (pinfunction "A13_26") (pintype "bidirectional"))
    )
    (net (code "75") (name "unconnected-(U$4-A14-Pad1)") (class "Default")
      (node (ref "U$4") (pin "1") (pinfunction "A14_1") (pintype "bidirectional"))
    )
    (net (code "76") (name "unconnected-(U$5-MLB-Pad5)") (class "Default")
      (node (ref "U$5") (pin "5") (pinfunction "MLB_5") (pintype "bidirectional"))
    )
    (net (code "77") (name "unconnected-(U$5-NC-Pad35)") (class "Default")
      (node (ref "U$5") (pin "35") (pinfunction "NC_35") (pintype "bidirectional"))
    )
    (net (code "78") (name "unconnected-(U$5-PHI1O-Pad3)") (class "Default")
      (node (ref "U$5") (pin "3") (pinfunction "PHI1O_3") (pintype "bidirectional"))
    )
    (net (code "79") (name "unconnected-(U$5-PHI2C-Pad39)") (class "Default")
      (node (ref "U$5") (pin "39") (pinfunction "PHI2C_39") (pintype "bidirectional"))
    )
    (net (code "80") (name "unconnected-(U$5-SYNC-Pad7)") (class "Default")
      (node (ref "U$5") (pin "7") (pinfunction "SYNC_7") (pintype "bidirectional"))
    )
    (net (code "81") (name "unconnected-(U$5-VPB-Pad1)") (class "Default")
      (node (ref "U$5") (pin "1") (pinfunction "VPB_1") (pintype "bidirectional"))
    )
  )
)
